# basePCB.net
KiCad netlist of a schematic drawn in EAGLE
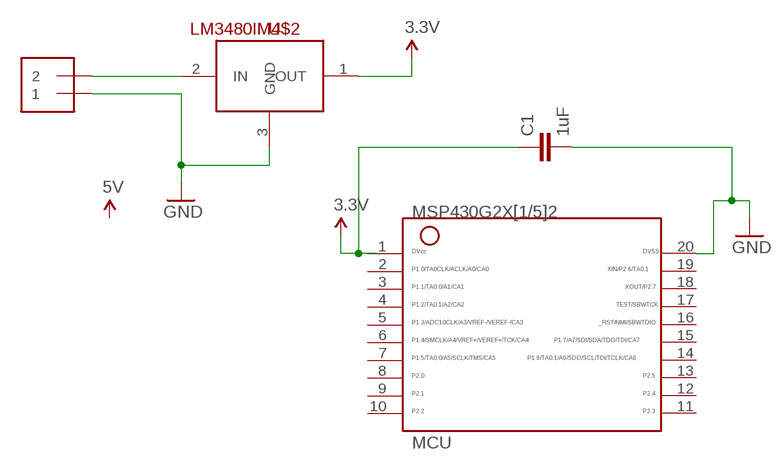
[diagram p0: schematic, sheet 1]

(export (version "E")
  (design (tool "Eeschema 10.0.6"))
  (components
    (comp (ref "C1")
      (value "1uF")
      (footprint "eagle-import:CAP-PTH-SMALL")
      (libsource (lib "eagle-import") (part "CAPPTH"))
    )
    (comp (ref "J1")
      (value "1X2-3.5MM")
      (footprint "eagle-import:1X2-3.5MM")
      (libsource (lib "eagle-import") (part "1X2-3.5MM"))
    )
    (comp (ref "MCU")
      (value "G2X[1/5]2---N20")
      (footprint "eagle-import:N20")
      (libsource (lib "eagle-import") (part "G2X[1/5]2---N20"))
    )
    (comp (ref "U$2")
      (value "LM3480IM4")
      (footprint "eagle-import:SOT23-3")
      (libsource (lib "eagle-import") (part "LM3480IM4"))
    )
  )
  (nets
    (net (code "1") (name "3.3V") (class "Default")
      (node (ref "C1") (pin "1") (pinfunction "1_1") (pintype "passive"))
      (node (ref "U$2") (pin "1") (pinfunction "OUT_1") (pintype "bidirectional"))
    )
    (net (code "3") (name "GND") (class "Default")
      (node (ref "C1") (pin "2") (pinfunction "2_2") (pintype "passive"))
      (node (ref "J1") (pin "1") (pinfunction "1_1") (pintype "passive"))
      (node (ref "MCU") (pin "20") (pinfunction "20_20") (pintype "bidirectional"))
      (node (ref "U$2") (pin "3") (pinfunction "GND_3") (pintype "bidirectional"))
    )
    (net (code "4") (name "Net-(U$2-IN)") (class "Default")
      (node (ref "J1") (pin "2") (pinfunction "2_2") (pintype "passive"))
      (node (ref "U$2") (pin "2") (pinfunction "IN_2") (pintype "bidirectional"))
    )
    (net (code "5") (name "unconnected-(MCU-Pad1)") (class "Default")
      (node (ref "MCU") (pin "1") (pinfunction "1_1") (pintype "bidirectional"))
    )
    (net (code "6") (name "unconnected-(MCU-Pad2)") (class "Default")
      (node (ref "MCU") (pin "2") (pinfunction "2_2") (pintype "bidirectional"))
    )
    (net (code "7") (name "unconnected-(MCU-Pad3)") (class "Default")
      (node (ref "MCU") (pin "3") (pinfunction "3_3") (pintype "bidirectional"))
    )
    (net (code "8") (name "unconnected-(MCU-Pad4)") (class "Default")
      (node (ref "MCU") (pin "4") (pinfunction "4_4") (pintype "bidirectional"))
    )
    (net (code "9") (name "unconnected-(MCU-Pad5)") (class "Default")
      (node (ref "MCU") (pin "5") (pinfunction "5_5") (pintype "bidirectional"))
    )
    (net (code "10") (name "unconnected-(MCU-Pad6)") (class "Default")
      (node (ref "MCU") (pin "6") (pinfunction "6_6") (pintype "bidirectional"))
    )
    (net (code "11") (name "unconnected-(MCU-Pad7)") (class "Default")
      (node (ref "MCU") (pin "7") (pinfunction "7_7") (pintype "bidirectional"))
    )
    (net (code "12") (name "unconnected-(MCU-Pad8)") (class "Default")
      (node (ref "MCU") (pin "8") (pinfunction "8_8") (pintype "bidirectional"))
    )
    (net (code "13") (name "unconnected-(MCU-Pad9)") (class "Default")
      (node (ref "MCU") (pin "9") (pinfunction "9_9") (pintype "bidirectional"))
    )
    (net (code "14") (name "unconnected-(MCU-Pad10)") (class "Default")
      (node (ref "MCU") (pin "10") (pinfunction "10_10") (pintype "bidirectional"))
    )
    (net (code "15") (name "unconnected-(MCU-Pad11)") (class "Default")
      (node (ref "MCU") (pin "11") (pinfunction "11_11") (pintype "bidirectional"))
    )
    (net (code "16") (name "unconnected-(MCU-Pad12)") (class "Default")
      (node (ref "MCU") (pin "12") (pinfunction "12_12") (pintype "bidirectional"))
    )
    (net (code "17") (name "unconnected-(MCU-Pad13)") (class "Default")
      (node (ref "MCU") (pin "13") (pinfunction "13_13") (pintype "bidirectional"))
    )
    (net (code "18") (name "unconnected-(MCU-Pad14)") (class "Default")
      (node (ref "MCU") (pin "14") (pinfunction "14_14") (pintype "bidirectional"))
    )
    (net (code "19") (name "unconnected-(MCU-Pad15)") (class "Default")
      (node (ref "MCU") (pin "15") (pinfunction "15_15") (pintype "bidirectional"))
    )
    (net (code "20") (name "unconnected-(MCU-Pad16)") (class "Default")
      (node (ref "MCU") (pin "16") (pinfunction "16_16") (pintype "bidirectional"))
    )
    (net (code "21") (name "unconnected-(MCU-Pad17)") (class "Default")
      (node (ref "MCU") (pin "17") (pinfunction "17_17") (pintype "bidirectional"))
    )
    (net (code "22") (name "unconnected-(MCU-Pad18)") (class "Default")
      (node (ref "MCU") (pin "18") (pinfunction "18_18") (pintype "bidirectional"))
    )
    (net (code "23") (name "unconnected-(MCU-Pad19)") (class "Default")
      (node (ref "MCU") (pin "19") (pinfunction "19_19") (pintype "bidirectional"))
    )
  )
)
